# 02_power.net
KiCad netlist of a schematic drawn in Altium Designer
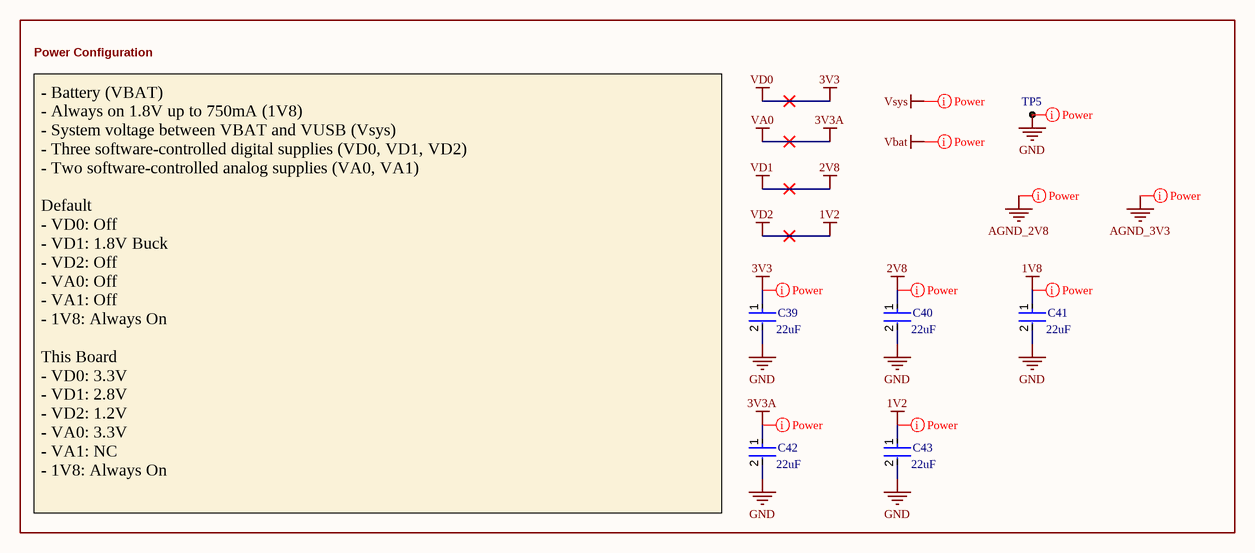
[diagram p0: 02_power.SchDoc]

(export (version "E")
  (design (tool "Eeschema 10.0.6"))
  (components
    (comp (ref "C39")
      (value "GRM158R60J226ME01D")
      (footprint "FP-GRM158-0_2-IPC_A")
      (description "CAP CER 22UF 6.3V X5R 0402")
      (fields
        (field (name "MANUFACTURER") "Murata")
        (field (name "CAPACITANCE") "22uF")
        (field (name "TOLERANCE") "20%")
      )
      (libsource (lib "Altium Content Vault") (part "b4654b650e69147ec39a6b967a45e02"))
    )
    (comp (ref "C40")
      (value "GRM158R60J226ME01D")
      (footprint "FP-GRM158-0_2-IPC_A")
      (description "CAP CER 22UF 6.3V X5R 0402")
      (fields
        (field (name "MANUFACTURER") "Murata")
        (field (name "CAPACITANCE") "22uF")
        (field (name "TOLERANCE") "20%")
      )
      (libsource (lib "Altium Content Vault") (part "b4654b650e69147ec39a6b967a45e02"))
    )
    (comp (ref "C41")
      (value "GRM158R60J226ME01D")
      (footprint "FP-GRM158-0_2-IPC_A")
      (description "CAP CER 22UF 6.3V X5R 0402")
      (fields
        (field (name "MANUFACTURER") "Murata")
        (field (name "CAPACITANCE") "22uF")
        (field (name "TOLERANCE") "20%")
      )
      (libsource (lib "Altium Content Vault") (part "b4654b650e69147ec39a6b967a45e02"))
    )
    (comp (ref "C42")
      (value "GRM158R60J226ME01D")
      (footprint "FP-GRM158-0_2-IPC_A")
      (description "CAP CER 22UF 6.3V X5R 0402")
      (fields
        (field (name "MANUFACTURER") "Murata")
        (field (name "CAPACITANCE") "22uF")
        (field (name "TOLERANCE") "20%")
      )
      (libsource (lib "Altium Content Vault") (part "b4654b650e69147ec39a6b967a45e02"))
    )
    (comp (ref "C43")
      (value "GRM158R60J226ME01D")
      (footprint "FP-GRM158-0_2-IPC_A")
      (description "CAP CER 22UF 6.3V X5R 0402")
      (fields
        (field (name "MANUFACTURER") "Murata")
        (field (name "CAPACITANCE") "22uF")
        (field (name "TOLERANCE") "20%")
      )
      (libsource (lib "Altium Content Vault") (part "b4654b650e69147ec39a6b967a45e02"))
    )
    (comp (ref "TP5")
      (value "Test Pad")
      (footprint "Pad-0.6mm")
      (description "0.6mm SMT Test Pad")
      (libsource (lib "ETHZ Vault") (part "Test Pad"))
    )
  )
  (nets
    (net (code "1") (name "1V2") (class "Default")
      (node (ref "C43") (pin "1") (pinfunction "1_1") (pintype "passive"))
    )
    (net (code "2") (name "1V8") (class "Default")
      (node (ref "C41") (pin "1") (pinfunction "1_1") (pintype "passive"))
    )
    (net (code "3") (name "2V8") (class "Default")
      (node (ref "C40") (pin "1") (pinfunction "1_1") (pintype "passive"))
    )
    (net (code "4") (name "3V3") (class "Default")
      (node (ref "C39") (pin "1") (pinfunction "1_1") (pintype "passive"))
    )
    (net (code "5") (name "3V3A") (class "Default")
      (node (ref "C42") (pin "1") (pinfunction "1_1") (pintype "passive"))
    )
    (net (code "8") (name "GND") (class "Default")
      (node (ref "C39") (pin "2") (pinfunction "2_2") (pintype "passive"))
      (node (ref "C40") (pin "2") (pinfunction "2_2") (pintype "passive"))
      (node (ref "C41") (pin "2") (pinfunction "2_2") (pintype "passive"))
      (node (ref "C42") (pin "2") (pinfunction "2_2") (pintype "passive"))
      (node (ref "C43") (pin "2") (pinfunction "2_2") (pintype "passive"))
      (node (ref "TP5") (pin "1") (pinfunction "1_1") (pintype "passive"))
    )
  )
)
